# 01_Arduino_IO.net
KiCad netlist of a schematic drawn in Altium Designer
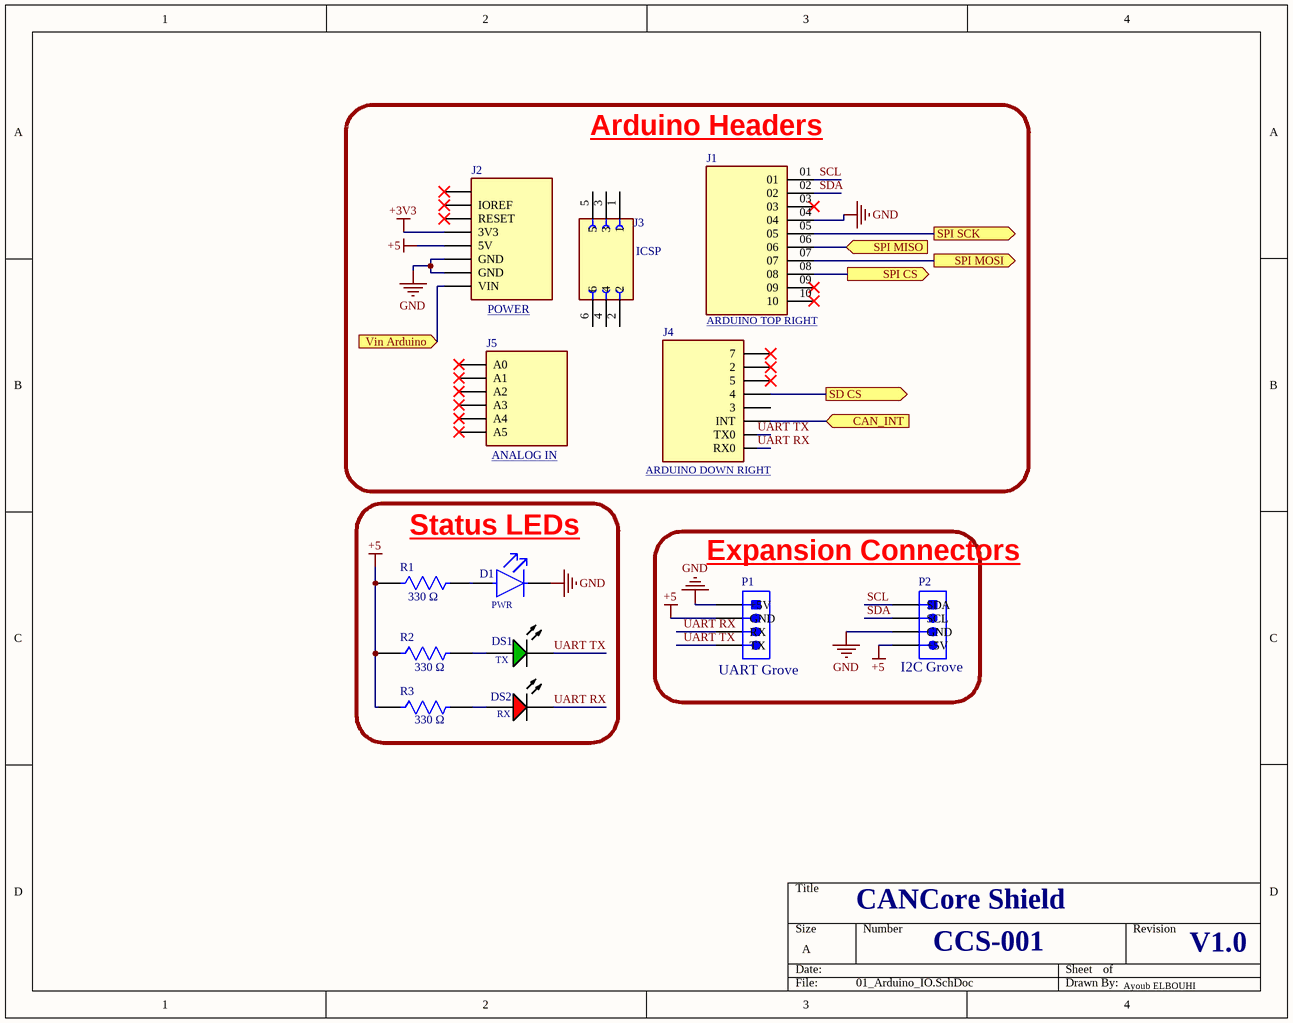
[diagram p0: 01_Arduino_IO.SchDoc]

(export (version "E")
  (design (tool "Eeschema 10.0.6"))
  (components
    (comp (ref "D1")
      (value "PWR")
      (footprint "FP-LTST-C170KFKT-MFG")
      (description "LED ORANGE CLEAR SMD")
      (libsource (lib "Altium Content Vault") (part "8706943c75ba83719d021d2fdc84c58"))
    )
    (comp (ref "DS1")
      (value "TX")
      (footprint "LTST-LTST-C170KGKT-2_V")
      (description "Ultra Bright AlInGaP Chip LED, 75 mW, -55 to 85 degC, 2-Pin SMD (0805), RoHS, Tape and Reel")
      (fields (field (name "MANUFACTURER") "Lite-On"))
      (libsource (lib "Altium Content Vault") (part "LED-GREEN-KA-2"))
    )
    (comp (ref "DS2")
      (value "RX")
      (footprint "LTST-C170KRKT_V")
      (description "LED Red, 75 mW, 54 mcd, -55 to 85 degC, 2-Pin SMD, RoHS, Tape and Reel")
      (fields (field (name "MANUFACTURER") "Lite-On"))
      (libsource (lib "Altium Content Vault") (part "LED-RED-AK-2"))
    )
    (comp (ref "J1")
      (value "ARDUINO TOP RIGHT")
      (footprint "SAMTEC_ESQ-110-14-G-S")
      (fields (field (name "MP") "ESQ-110-14-G-S") (field (name "MF") "Samtec"))
      (libsource (lib "ESQ-110-14-G-S") (part "ESQ-110-14-G-S"))
    )
    (comp (ref "J2")
      (value "POWER")
      (footprint "SAMTEC_ESQ-108-14-G-S")
      (fields (field (name "MP") "ESQ-108-14-G-S"))
      (libsource (lib "") (part "ESQ-108-14-G-S_1"))
    )
    (comp (ref "J3")
      (value "ICSP")
      (footprint "SULLINS_PPTC032LFBN-RC")
      (description "6 Position Header Connector 0.100 (2.54mm) Through Hole Tin")
      (fields (field (name "MF") "Sullins Connector Solutions") (field (name "MP") "PPTC032LFBN-RC"))
      (libsource (lib "PPTC032LFBN-RC") (part "PPTC032LFBN-RC"))
    )
    (comp (ref "J4")
      (value "ARDUINO DOWN RIGHT")
      (footprint "SAMTEC_ESQ-108-14-G-S")
      (fields (field (name "MP") "ESQ-108-14-G-S"))
      (libsource (lib "ESQ-108-14-G-S") (part "ESQ-108-14-G-S"))
    )
    (comp (ref "J5")
      (value "ANALOG IN")
      (footprint "SAMTEC_ESQ-106-14-G-S")
      (fields (field (name "MP") "ESQ-106-14-G-S"))
      (libsource (lib "ESQ-106-14-G-S") (part "ESQ-106-14-G-S"))
    )
    (comp (ref "P1")
      (value "UART Grove")
      (footprint "JST-B4B-PH-K-S_V")
      (fields (field (name "MANUFACTURER") "JST"))
      (libsource (lib "Altium Content Vault") (part "CN-1P-M-R4"))
    )
    (comp (ref "P2")
      (value "I2C Grove")
      (footprint "JST-B4B-PH-K-S_V")
      (fields (field (name "MANUFACTURER") "JST"))
      (libsource (lib "Altium Content Vault") (part "CN-1P-M-R4"))
    )
    (comp (ref "R1")
      (value "330 Ω")
      (footprint "FP-RT0603-MFG")
      (description "RES SMD 330 OHM 1% 1/10W 0603")
      (fields
        (field (name "TOLERANCE") "0.01")
        (field (name "OCTOPART") "https://octopart.com/rt0603frd07330rl-yageo-71395358")
      )
      (libsource (lib "Altium Content Vault") (part "1029c3af85768c4190bb7ad29bc67b5"))
    )
    (comp (ref "R2")
      (value "330 Ω")
      (footprint "FP-RT0603-MFG")
      (description "RES SMD 330 OHM 1% 1/10W 0603")
      (fields
        (field (name "TOLERANCE") "0.01")
        (field (name "OCTOPART") "https://octopart.com/rt0603frd07330rl-yageo-71395358")
      )
      (libsource (lib "Altium Content Vault") (part "1029c3af85768c4190bb7ad29bc67b5"))
    )
    (comp (ref "R3")
      (value "330 Ω")
      (footprint "FP-RT0603-MFG")
      (description "RES SMD 330 OHM 1% 1/10W 0603")
      (fields
        (field (name "TOLERANCE") "0.01")
        (field (name "OCTOPART") "https://octopart.com/rt0603frd07330rl-yageo-71395358")
      )
      (libsource (lib "Altium Content Vault") (part "1029c3af85768c4190bb7ad29bc67b5"))
    )
  )
  (nets
    (net (code "1") (name "+3V3") (class "Default")
      (node (ref "J2") (pin "04") (pinfunction "3V3_04") (pintype "passive"))
    )
    (net (code "2") (name "+5") (class "Default")
      (node (ref "J2") (pin "05") (pinfunction "5V_05") (pintype "passive"))
      (node (ref "P1") (pin "2") (pinfunction "SCL_2") (pintype "passive"))
      (node (ref "P2") (pin "4") (pinfunction "+5V_4") (pintype "passive"))
      (node (ref "R1") (pin "1") (pinfunction "1_1") (pintype "passive"))
      (node (ref "R2") (pin "1") (pinfunction "1_1") (pintype "passive"))
      (node (ref "R3") (pin "1") (pinfunction "1_1") (pintype "passive"))
    )
    (net (code "3") (name "/CAN_INT") (class "Default")
      (node (ref "J4") (pin "06") (pinfunction "INT_06") (pintype "passive"))
    )
    (net (code "4") (name "/SCL") (class "Default")
      (node (ref "J1") (pin "01") (pinfunction "01_01") (pintype "passive"))
      (node (ref "P2") (pin "1") (pinfunction "SDA_1") (pintype "passive"))
    )
    (net (code "5") (name "/SD CS") (class "Default")
      (node (ref "J4") (pin "04") (pinfunction "4_04") (pintype "passive"))
    )
    (net (code "6") (name "/SDA") (class "Default")
      (node (ref "J1") (pin "02") (pinfunction "02_02") (pintype "passive"))
      (node (ref "P2") (pin "2") (pinfunction "SCL_2") (pintype "passive"))
    )
    (net (code "7") (name "/SPI CS") (class "Default")
      (node (ref "J1") (pin "08") (pinfunction "08_08") (pintype "passive"))
    )
    (net (code "8") (name "/SPI MISO") (class "Default")
      (node (ref "J1") (pin "06") (pinfunction "06_06") (pintype "passive"))
    )
    (net (code "9") (name "/SPI MOSI") (class "Default")
      (node (ref "J1") (pin "07") (pinfunction "07_07") (pintype "passive"))
    )
    (net (code "10") (name "/SPI SCK") (class "Default")
      (node (ref "J1") (pin "05") (pinfunction "05_05") (pintype "passive"))
    )
    (net (code "11") (name "/UART RX") (class "Default")
      (node (ref "DS2") (pin "2") (pinfunction "K_2") (pintype "passive"))
      (node (ref "J4") (pin "08") (pinfunction "RX0_08") (pintype "passive"))
      (node (ref "P1") (pin "3") (pinfunction "GND_3") (pintype "passive"))
    )
    (net (code "12") (name "/UART TX") (class "Default")
      (node (ref "DS1") (pin "1") (pinfunction "K_1") (pintype "passive"))
      (node (ref "J4") (pin "07") (pinfunction "TX0_07") (pintype "passive"))
      (node (ref "P1") (pin "4") (pinfunction "+5V_4") (pintype "passive"))
    )
    (net (code "13") (name "/Vin Arduino") (class "Default")
      (node (ref "J2") (pin "08") (pinfunction "VIN_08") (pintype "passive"))
    )
    (net (code "14") (name "GND") (class "Default")
      (node (ref "D1") (pin "1") (pinfunction "C_1") (pintype "passive"))
      (node (ref "J1") (pin "04") (pinfunction "04_04") (pintype "passive"))
      (node (ref "J2") (pin "06") (pinfunction "GND_06") (pintype "passive"))
      (node (ref "J2") (pin "07") (pinfunction "GND_07") (pintype "passive"))
      (node (ref "P1") (pin "1") (pinfunction "SDA_1") (pintype "passive"))
      (node (ref "P2") (pin "3") (pinfunction "GND_3") (pintype "passive"))
    )
    (net (code "15") (name "Net-(D1-A)") (class "Default")
      (node (ref "D1") (pin "2") (pinfunction "A_2") (pintype "passive"))
      (node (ref "R1") (pin "2") (pinfunction "2_2") (pintype "passive"))
    )
    (net (code "16") (name "Net-(DS1-A)") (class "Default")
      (node (ref "DS1") (pin "2") (pinfunction "A_2") (pintype "passive"))
      (node (ref "R2") (pin "2") (pinfunction "2_2") (pintype "passive"))
    )
    (net (code "17") (name "Net-(DS2-A)") (class "Default")
      (node (ref "DS2") (pin "1") (pinfunction "A_1") (pintype "passive"))
      (node (ref "R3") (pin "2") (pinfunction "2_2") (pintype "passive"))
    )
    (net (code "18") (name "unconnected-(J1-Pad03)") (class "Default")
      (node (ref "J1") (pin "03") (pinfunction "03_03") (pintype "passive+no_connect"))
    )
    (net (code "19") (name "unconnected-(J1-Pad09)") (class "Default")
      (node (ref "J1") (pin "09") (pinfunction "09_09") (pintype "passive+no_connect"))
    )
    (net (code "20") (name "unconnected-(J1-Pad10)") (class "Default")
      (node (ref "J1") (pin "10") (pinfunction "10_10") (pintype "passive+no_connect"))
    )
    (net (code "21") (name "unconnected-(J2-IOREF-Pad02)") (class "Default")
      (node (ref "J2") (pin "02") (pinfunction "IOREF_02") (pintype "passive+no_connect"))
    )
    (net (code "22") (name "unconnected-(J2-Pad01)") (class "Default")
      (node (ref "J2") (pin "01") (pintype "passive+no_connect"))
    )
    (net (code "23") (name "unconnected-(J2-RESET-Pad03)") (class "Default")
      (node (ref "J2") (pin "03") (pinfunction "RESET_03") (pintype "passive+no_connect"))
    )
    (net (code "24") (name "unconnected-(J3-Pad1)") (class "Default")
      (node (ref "J3") (pin "1") (pinfunction "1_1") (pintype "passive"))
    )
    (net (code "25") (name "unconnected-(J3-Pad2)") (class "Default")
      (node (ref "J3") (pin "2") (pinfunction "2_2") (pintype "passive"))
    )
    (net (code "26") (name "unconnected-(J3-Pad3)") (class "Default")
      (node (ref "J3") (pin "3") (pinfunction "3_3") (pintype "passive"))
    )
    (net (code "27") (name "unconnected-(J3-Pad4)") (class "Default")
      (node (ref "J3") (pin "4") (pinfunction "4_4") (pintype "passive"))
    )
    (net (code "28") (name "unconnected-(J3-Pad5)") (class "Default")
      (node (ref "J3") (pin "5") (pinfunction "5_5") (pintype "passive"))
    )
    (net (code "29") (name "unconnected-(J3-Pad6)") (class "Default")
      (node (ref "J3") (pin "6") (pinfunction "6_6") (pintype "passive"))
    )
    (net (code "30") (name "unconnected-(J4-2-Pad02)") (class "Default")
      (node (ref "J4") (pin "02") (pinfunction "2_02") (pintype "passive+no_connect"))
    )
    (net (code "31") (name "unconnected-(J4-3-Pad05)") (class "Default")
      (node (ref "J4") (pin "05") (pinfunction "3_05") (pintype "passive"))
    )
    (net (code "32") (name "unconnected-(J4-5-Pad03)") (class "Default")
      (node (ref "J4") (pin "03") (pinfunction "5_03") (pintype "passive+no_connect"))
    )
    (net (code "33") (name "unconnected-(J4-7-Pad01)") (class "Default")
      (node (ref "J4") (pin "01") (pinfunction "7_01") (pintype "passive+no_connect"))
    )
    (net (code "34") (name "unconnected-(J5-A0-Pad01)") (class "Default")
      (node (ref "J5") (pin "01") (pinfunction "A0_01") (pintype "passive+no_connect"))
    )
    (net (code "35") (name "unconnected-(J5-A1-Pad02)") (class "Default")
      (node (ref "J5") (pin "02") (pinfunction "A1_02") (pintype "passive+no_connect"))
    )
    (net (code "36") (name "unconnected-(J5-A2-Pad03)") (class "Default")
      (node (ref "J5") (pin "03") (pinfunction "A2_03") (pintype "passive+no_connect"))
    )
    (net (code "37") (name "unconnected-(J5-A3-Pad04)") (class "Default")
      (node (ref "J5") (pin "04") (pinfunction "A3_04") (pintype "passive+no_connect"))
    )
    (net (code "38") (name "unconnected-(J5-A4-Pad05)") (class "Default")
      (node (ref "J5") (pin "05") (pinfunction "A4_05") (pintype "passive+no_connect"))
    )
    (net (code "39") (name "unconnected-(J5-A5-Pad06)") (class "Default")
      (node (ref "J5") (pin "06") (pinfunction "A5_06") (pintype "passive+no_connect"))
    )
  )
)
